# Led_Chaser.net
KiCad netlist of a schematic drawn in Altium Designer
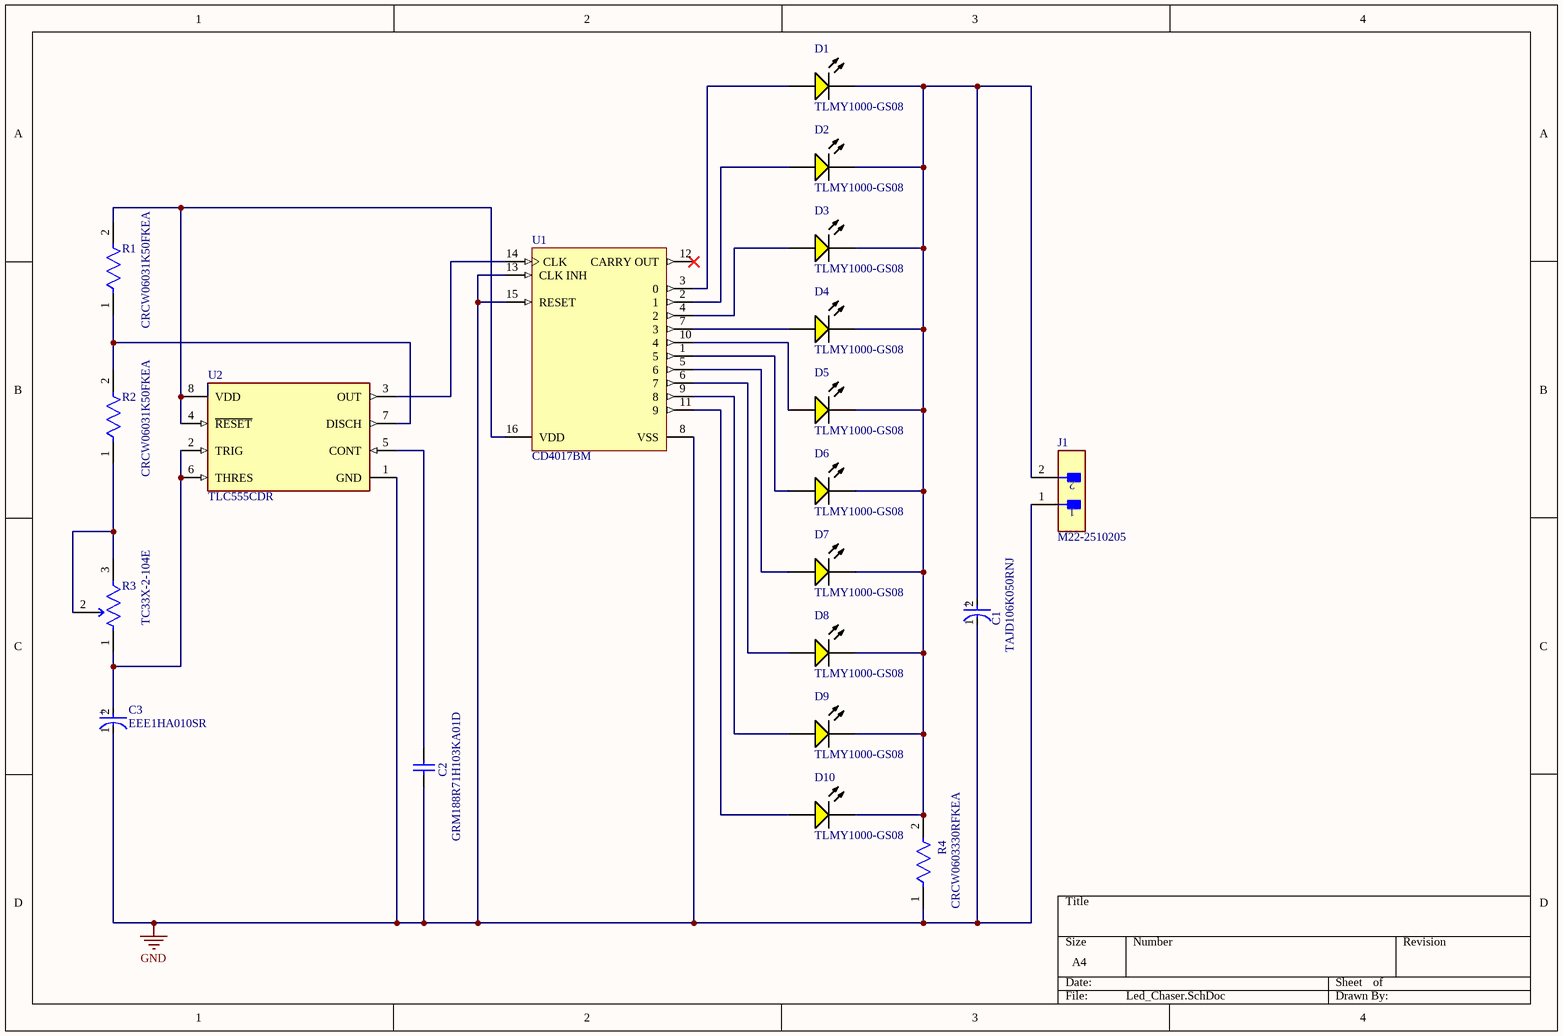
[diagram p0: Led_Chaser.SchDoc]

(export (version "E")
  (design (tool "Eeschema 10.0.6"))
  (components
    (comp (ref "C1")
      (value "TAJD106K050RNJ")
      (footprint "FP-TAJD-MFG")
      (description "10uF 50V  ±10% 800mΩ 2917  SMD Tantalum Capacitor")
      (fields (field (name "VOLTAGE") "50V") (field (name "TOLERANCE") "10%"))
      (libsource (lib "Altium Content Vault") (part "a00bbbee19879c290e62620ae7e47b1"))
    )
    (comp (ref "C2")
      (value "GRM188R71H103KA01D")
      (footprint "CAPC1608X90X35ML10T15")
      (description "Chip Capacitor, 10 nF, +/- 10%, 50 V, -55 to 125 degC, 0603 (1608 Metric), RoHS, Tape and Reel")
      (fields (field (name "VOLTAGE") "50V") (field (name "TOLERANCE") "10%"))
      (libsource (lib "Altium Content Vault") (part "CAP-NP-2"))
    )
    (comp (ref "C3")
      (value "EEE1HA010SR")
      (footprint "FP-SB-MFG")
      (description "CAP ALUM 1UF 20% 50V SMD")
      (fields (field (name "TOLERANCE") "20%") (field (name "VOLTAGE") "50V"))
      (libsource (lib "Altium Content Vault") (part "203bc49f2ac43e59fd269a8c329ed05"))
    )
    (comp (ref "D1")
      (value "TLMY1000-GS08")
      (footprint "VISH-TLMY1000_V")
      (description "Low Current LED, 40 mW, -40 to 100 degC, 2-Pin SMD, RoHS, Tape and Reel")
      (fields (field (name "MANUFACTURER") "Vishay"))
      (libsource (lib "Altium Content Vault") (part "LED-YELLOW-AK-2"))
    )
    (comp (ref "D2")
      (value "TLMY1000-GS08")
      (footprint "VISH-TLMY1000_V")
      (description "Low Current LED, 40 mW, -40 to 100 degC, 2-Pin SMD, RoHS, Tape and Reel")
      (fields (field (name "MANUFACTURER") "Vishay"))
      (libsource (lib "Altium Content Vault") (part "LED-YELLOW-AK-2"))
    )
    (comp (ref "D3")
      (value "TLMY1000-GS08")
      (footprint "VISH-TLMY1000_V")
      (description "Low Current LED, 40 mW, -40 to 100 degC, 2-Pin SMD, RoHS, Tape and Reel")
      (fields (field (name "MANUFACTURER") "Vishay"))
      (libsource (lib "Altium Content Vault") (part "LED-YELLOW-AK-2"))
    )
    (comp (ref "D4")
      (value "TLMY1000-GS08")
      (footprint "VISH-TLMY1000_V")
      (description "Low Current LED, 40 mW, -40 to 100 degC, 2-Pin SMD, RoHS, Tape and Reel")
      (fields (field (name "MANUFACTURER") "Vishay"))
      (libsource (lib "Altium Content Vault") (part "LED-YELLOW-AK-2"))
    )
    (comp (ref "D5")
      (value "TLMY1000-GS08")
      (footprint "VISH-TLMY1000_V")
      (description "Low Current LED, 40 mW, -40 to 100 degC, 2-Pin SMD, RoHS, Tape and Reel")
      (fields (field (name "MANUFACTURER") "Vishay"))
      (libsource (lib "Altium Content Vault") (part "LED-YELLOW-AK-2"))
    )
    (comp (ref "D6")
      (value "TLMY1000-GS08")
      (footprint "VISH-TLMY1000_V")
      (description "Low Current LED, 40 mW, -40 to 100 degC, 2-Pin SMD, RoHS, Tape and Reel")
      (fields (field (name "MANUFACTURER") "Vishay"))
      (libsource (lib "Altium Content Vault") (part "LED-YELLOW-AK-2"))
    )
    (comp (ref "D7")
      (value "TLMY1000-GS08")
      (footprint "VISH-TLMY1000_V")
      (description "Low Current LED, 40 mW, -40 to 100 degC, 2-Pin SMD, RoHS, Tape and Reel")
      (fields (field (name "MANUFACTURER") "Vishay"))
      (libsource (lib "Altium Content Vault") (part "LED-YELLOW-AK-2"))
    )
    (comp (ref "D8")
      (value "TLMY1000-GS08")
      (footprint "VISH-TLMY1000_V")
      (description "Low Current LED, 40 mW, -40 to 100 degC, 2-Pin SMD, RoHS, Tape and Reel")
      (fields (field (name "MANUFACTURER") "Vishay"))
      (libsource (lib "Altium Content Vault") (part "LED-YELLOW-AK-2"))
    )
    (comp (ref "D9")
      (value "TLMY1000-GS08")
      (footprint "VISH-TLMY1000_V")
      (description "Low Current LED, 40 mW, -40 to 100 degC, 2-Pin SMD, RoHS, Tape and Reel")
      (fields (field (name "MANUFACTURER") "Vishay"))
      (libsource (lib "Altium Content Vault") (part "LED-YELLOW-AK-2"))
    )
    (comp (ref "D10")
      (value "TLMY1000-GS08")
      (footprint "VISH-TLMY1000_V")
      (description "Low Current LED, 40 mW, -40 to 100 degC, 2-Pin SMD, RoHS, Tape and Reel")
      (fields (field (name "MANUFACTURER") "Vishay"))
      (libsource (lib "Altium Content Vault") (part "LED-YELLOW-AK-2"))
    )
    (comp (ref "J1")
      (value "M22-2510205")
      (footprint "FP-M22-2510205-MFG")
      (description "CONN HEADER VERT 2POS 2MM")
      (fields
        (field (name "MANUFACTURER") "Harwin")
        (field (name "OCTOPART") "https://octopart.com/m22-2510205-harwin-2538221")
      )
      (libsource (lib "Altium Content Vault") (part "3bc925449376181038e59eaffc5286c"))
    )
    (comp (ref "R1")
      (value "CRCW06031K50FKEA")
      (footprint "FP-CRCW0603-e3-IPC_A")
      (description "RES Thick Film, 1.5kΩ, 1%, 0.1W, 100ppm/°C, 0603")
      (fields (field (name "TOLERANCE") "1%"))
      (libsource (lib "Altium Content Vault") (part "1029c3af85768c4190bb7ad29bc67b5"))
    )
    (comp (ref "R2")
      (value "CRCW06031K50FKEA")
      (footprint "FP-CRCW0603-e3-IPC_A")
      (description "RES Thick Film, 1.5kΩ, 1%, 0.1W, 100ppm/°C, 0603")
      (fields (field (name "TOLERANCE") "1%"))
      (libsource (lib "Altium Content Vault") (part "1029c3af85768c4190bb7ad29bc67b5"))
    )
    (comp (ref "R3")
      (value "TC33X-2-104E")
      (footprint "FP-TC33X-2-MFG")
      (description "TRIMMER 100K OHM 0.1W J LEAD TOP")
      (fields (field (name "TOLERANCE") "25%"))
      (libsource (lib "Altium Content Vault") (part "13357d81287629c2fd191d242cfa50c"))
    )
    (comp (ref "R4")
      (value "CRCW0603330RFKEA")
      (footprint "FP-CRCW0603-e3-MFG")
      (description "RES Thick Film, 330Ω, 1%, 0.1W, 100ppm/°C, 0603")
      (fields (field (name "TOLERANCE") "1%"))
      (libsource (lib "Altium Content Vault") (part "1029c3af85768c4190bb7ad29bc67b5"))
    )
    (comp (ref "U1")
      (value "CD4017BM")
      (footprint "D0016A_N")
      (description "CMOS Decade Counter with 10 Decoded Outputs, D0016A, TUBE")
      (fields
        (field (name "GENERIC PART NUMBER") "CD4017B")
        (field (name "MANUFACTURER") "Texas Instruments")
      )
      (libsource (lib "Altium Content Vault") (part "TI-CD4017B-16"))
    )
    (comp (ref "U2")
      (value "TLC555CDR")
      (footprint "FP-D0008A-IPC_B")
      (description "IC OSC SGL TIMER 2.1MHZ 8-SOIC")
      (libsource (lib "Altium Content Vault") (part "fd1638d23bf5e420a54176ee4f8e783"))
    )
  )
  (nets
    (net (code "1") (name "GND") (class "Default")
      (node (ref "C1") (pin "1") (pinfunction "C_1") (pintype "passive"))
      (node (ref "C2") (pin "1") (pinfunction "1_1") (pintype "passive"))
      (node (ref "C3") (pin "1") (pinfunction "C_1") (pintype "passive"))
      (node (ref "J1") (pin "1") (pinfunction "1_1") (pintype "passive"))
      (node (ref "R4") (pin "1") (pinfunction "1_1") (pintype "passive"))
      (node (ref "U1") (pin "13") (pinfunction "CLK_INH_13") (pintype "input"))
      (node (ref "U1") (pin "15") (pinfunction "RESET_15") (pintype "input"))
      (node (ref "U1") (pin "8") (pinfunction "VSS_8") (pintype "power_in"))
      (node (ref "U2") (pin "1") (pinfunction "GND_1") (pintype "power_in"))
    )
    (net (code "2") (name "Net-(C1-A)") (class "Default")
      (node (ref "C1") (pin "2") (pinfunction "A_2") (pintype "passive"))
      (node (ref "D1") (pin "2") (pinfunction "K_2") (pintype "passive"))
      (node (ref "D10") (pin "2") (pinfunction "K_2") (pintype "passive"))
      (node (ref "D2") (pin "2") (pinfunction "K_2") (pintype "passive"))
      (node (ref "D3") (pin "2") (pinfunction "K_2") (pintype "passive"))
      (node (ref "D4") (pin "2") (pinfunction "K_2") (pintype "passive"))
      (node (ref "D5") (pin "2") (pinfunction "K_2") (pintype "passive"))
      (node (ref "D6") (pin "2") (pinfunction "K_2") (pintype "passive"))
      (node (ref "D7") (pin "2") (pinfunction "K_2") (pintype "passive"))
      (node (ref "D8") (pin "2") (pinfunction "K_2") (pintype "passive"))
      (node (ref "D9") (pin "2") (pinfunction "K_2") (pintype "passive"))
      (node (ref "J1") (pin "2") (pinfunction "2_2") (pintype "passive"))
      (node (ref "R4") (pin "2") (pinfunction "2_2") (pintype "passive"))
    )
    (net (code "3") (name "Net-(C3-A)") (class "Default")
      (node (ref "C3") (pin "2") (pinfunction "A_2") (pintype "passive"))
      (node (ref "R3") (pin "1") (pinfunction "CCW_1") (pintype "passive"))
      (node (ref "U2") (pin "2") (pinfunction "TRIG_2") (pintype "input"))
      (node (ref "U2") (pin "6") (pinfunction "THRES_6") (pintype "input"))
    )
    (net (code "4") (name "Net-(D1-A)") (class "Default")
      (node (ref "D1") (pin "1") (pinfunction "A_1") (pintype "passive"))
      (node (ref "U1") (pin "3") (pinfunction "0_3") (pintype "output"))
    )
    (net (code "5") (name "Net-(D2-A)") (class "Default")
      (node (ref "D2") (pin "1") (pinfunction "A_1") (pintype "passive"))
      (node (ref "U1") (pin "2") (pinfunction "1_2") (pintype "output"))
    )
    (net (code "6") (name "Net-(D3-A)") (class "Default")
      (node (ref "D3") (pin "1") (pinfunction "A_1") (pintype "passive"))
      (node (ref "U1") (pin "4") (pinfunction "2_4") (pintype "output"))
    )
    (net (code "7") (name "Net-(D4-A)") (class "Default")
      (node (ref "D4") (pin "1") (pinfunction "A_1") (pintype "passive"))
      (node (ref "U1") (pin "7") (pinfunction "3_7") (pintype "output"))
    )
    (net (code "8") (name "Net-(D5-A)") (class "Default")
      (node (ref "D5") (pin "1") (pinfunction "A_1") (pintype "passive"))
      (node (ref "U1") (pin "10") (pinfunction "4_10") (pintype "output"))
    )
    (net (code "9") (name "Net-(D6-A)") (class "Default")
      (node (ref "D6") (pin "1") (pinfunction "A_1") (pintype "passive"))
      (node (ref "U1") (pin "1") (pinfunction "5_1") (pintype "output"))
    )
    (net (code "10") (name "Net-(D7-A)") (class "Default")
      (node (ref "D7") (pin "1") (pinfunction "A_1") (pintype "passive"))
      (node (ref "U1") (pin "5") (pinfunction "6_5") (pintype "output"))
    )
    (net (code "11") (name "Net-(D8-A)") (class "Default")
      (node (ref "D8") (pin "1") (pinfunction "A_1") (pintype "passive"))
      (node (ref "U1") (pin "6") (pinfunction "7_6") (pintype "output"))
    )
    (net (code "12") (name "Net-(D9-A)") (class "Default")
      (node (ref "D9") (pin "1") (pinfunction "A_1") (pintype "passive"))
      (node (ref "U1") (pin "9") (pinfunction "8_9") (pintype "output"))
    )
    (net (code "13") (name "Net-(D10-A)") (class "Default")
      (node (ref "D10") (pin "1") (pinfunction "A_1") (pintype "passive"))
      (node (ref "U1") (pin "11") (pinfunction "9_11") (pintype "output"))
    )
    (net (code "14") (name "Net-(R3-CW)") (class "Default")
      (node (ref "R2") (pin "1") (pinfunction "1_1") (pintype "passive"))
      (node (ref "R3") (pin "2") (pinfunction "WIPER_2") (pintype "passive"))
      (node (ref "R3") (pin "3") (pinfunction "CW_3") (pintype "passive"))
    )
    (net (code "15") (name "Net-(U1-CLK)") (class "Default")
      (node (ref "U1") (pin "14") (pinfunction "CLK_14") (pintype "input"))
      (node (ref "U2") (pin "3") (pinfunction "OUT_3") (pintype "output"))
    )
    (net (code "16") (name "Net-(U1-VDD)") (class "Default")
      (node (ref "R1") (pin "2") (pinfunction "2_2") (pintype "passive"))
      (node (ref "U1") (pin "16") (pinfunction "VDD_16") (pintype "power_in"))
      (node (ref "U2") (pin "4") (pinfunction "~{RESET}_4") (pintype "input"))
      (node (ref "U2") (pin "8") (pinfunction "VDD_8") (pintype "power_in"))
    )
    (net (code "17") (name "Net-(U2-CONT)") (class "Default")
      (node (ref "C2") (pin "2") (pinfunction "2_2") (pintype "passive"))
      (node (ref "U2") (pin "5") (pinfunction "CONT_5") (pintype "input"))
    )
    (net (code "18") (name "Net-(U2-DISCH)") (class "Default")
      (node (ref "R1") (pin "1") (pinfunction "1_1") (pintype "passive"))
      (node (ref "R2") (pin "2") (pinfunction "2_2") (pintype "passive"))
      (node (ref "U2") (pin "7") (pinfunction "DISCH_7") (pintype "output"))
    )
    (net (code "19") (name "unconnected-(U1-CARRY_OUT-Pad12)") (class "Default")
      (node (ref "U1") (pin "12") (pinfunction "CARRY_OUT_12") (pintype "output+no_connect"))
    )
  )
)
